# SCH_Encoder.net
KiCad netlist of a schematic drawn in EasyEDA
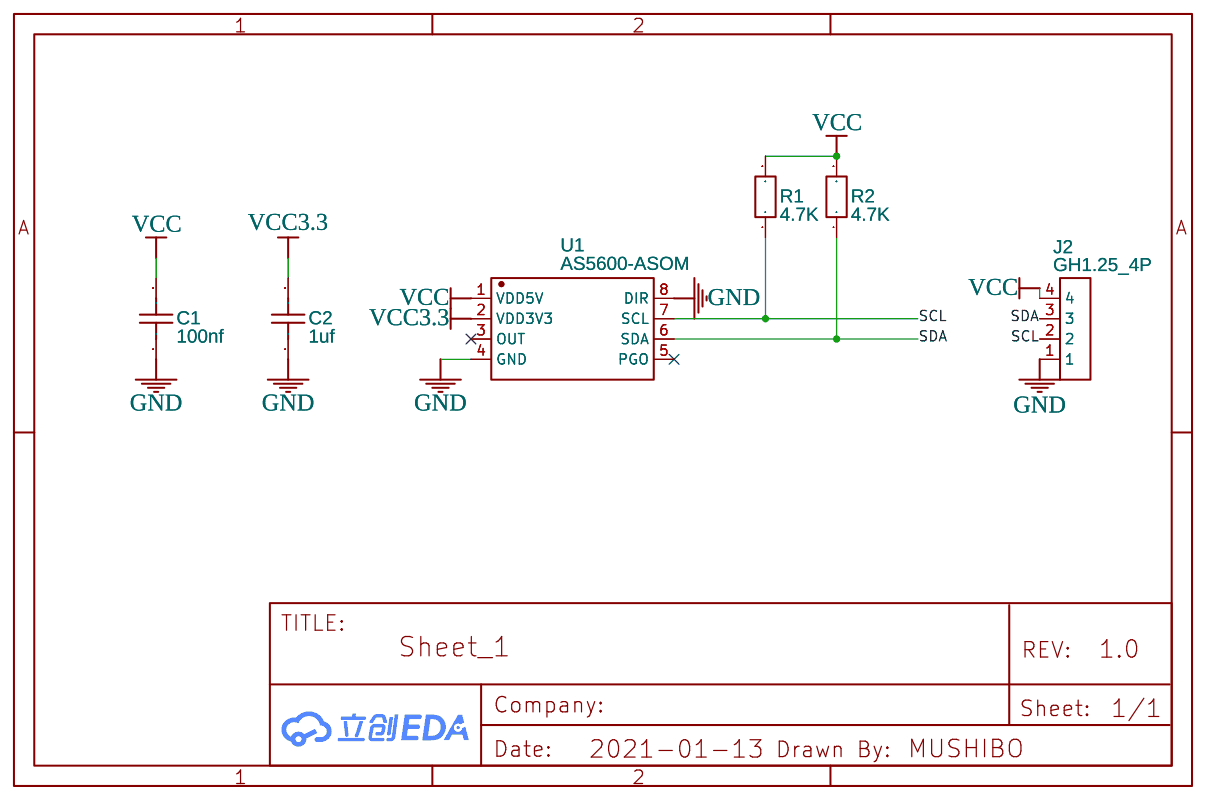
[diagram p0: schematic sheet]

(export (version "E")
  (design (tool "Eeschema 10.0.6"))
  (components
    (comp (ref "C1") (value "100nf") (libsource (lib "") (part "C_0603_US")))
    (comp (ref "C2") (value "1uf") (libsource (lib "") (part "C_0603_US")))
    (comp (ref "J2")
      (value "GH1.25_4P")
      (fields (field (name "Manufacturer") "Changjiang Connectors"))
      (libsource (lib "") (part "GH1.25_4P"))
    )
    (comp (ref "R1") (value "4.7K") (libsource (lib "") (part "R_0603_EU")))
    (comp (ref "R2") (value "4.7K") (libsource (lib "") (part "R_0603_EU")))
    (comp (ref "U1")
      (value "AS5600-ASOM")
      (fields (field (name "Manufacturer") "Ams"))
      (libsource (lib "") (part "AS5600-ASOM"))
    )
  )
  (nets
    (net (code "1") (name "/SCL") (class "Default")
      (node (ref "J2") (pin "2") (pinfunction "2_2") (pintype "unspecified"))
      (node (ref "R1") (pin "1") (pinfunction "1_1") (pintype "unspecified"))
      (node (ref "U1") (pin "7") (pinfunction "SCL_7") (pintype "unspecified"))
    )
    (net (code "2") (name "/SDA") (class "Default")
      (node (ref "J2") (pin "3") (pinfunction "3_3") (pintype "unspecified"))
      (node (ref "R2") (pin "1") (pinfunction "1_1") (pintype "unspecified"))
      (node (ref "U1") (pin "6") (pinfunction "SDA_6") (pintype "unspecified"))
    )
    (net (code "3") (name "GND") (class "Default")
      (node (ref "C1") (pin "1") (pinfunction "1_1") (pintype "unspecified"))
      (node (ref "C2") (pin "1") (pinfunction "1_1") (pintype "unspecified"))
      (node (ref "J2") (pin "1") (pinfunction "1_1") (pintype "unspecified"))
      (node (ref "U1") (pin "4") (pinfunction "GND_4") (pintype "unspecified"))
      (node (ref "U1") (pin "8") (pinfunction "DIR_8") (pintype "unspecified"))
    )
    (net (code "4") (name "VCC") (class "Default")
      (node (ref "C1") (pin "2") (pinfunction "2_2") (pintype "unspecified"))
      (node (ref "J2") (pin "4") (pinfunction "4_4") (pintype "unspecified"))
      (node (ref "R1") (pin "2") (pinfunction "2_2") (pintype "unspecified"))
      (node (ref "R2") (pin "2") (pinfunction "2_2") (pintype "unspecified"))
      (node (ref "U1") (pin "1") (pinfunction "VDD5V_1") (pintype "unspecified"))
    )
    (net (code "5") (name "VCC3.3") (class "Default")
      (node (ref "C2") (pin "2") (pinfunction "2_2") (pintype "unspecified"))
      (node (ref "U1") (pin "2") (pinfunction "VDD3V3_2") (pintype "unspecified"))
    )
    (net (code "6") (name "unconnected-(U1-OUT-Pad3)") (class "Default")
      (node (ref "U1") (pin "3") (pinfunction "OUT_3") (pintype "unspecified+no_connect"))
    )
    (net (code "7") (name "unconnected-(U1-PGO-Pad5)") (class "Default")
      (node (ref "U1") (pin "5") (pinfunction "PGO_5") (pintype "unspecified+no_connect"))
    )
  )
)
